# BLCTRL20.net
KiCad netlist of a schematic drawn in EAGLE
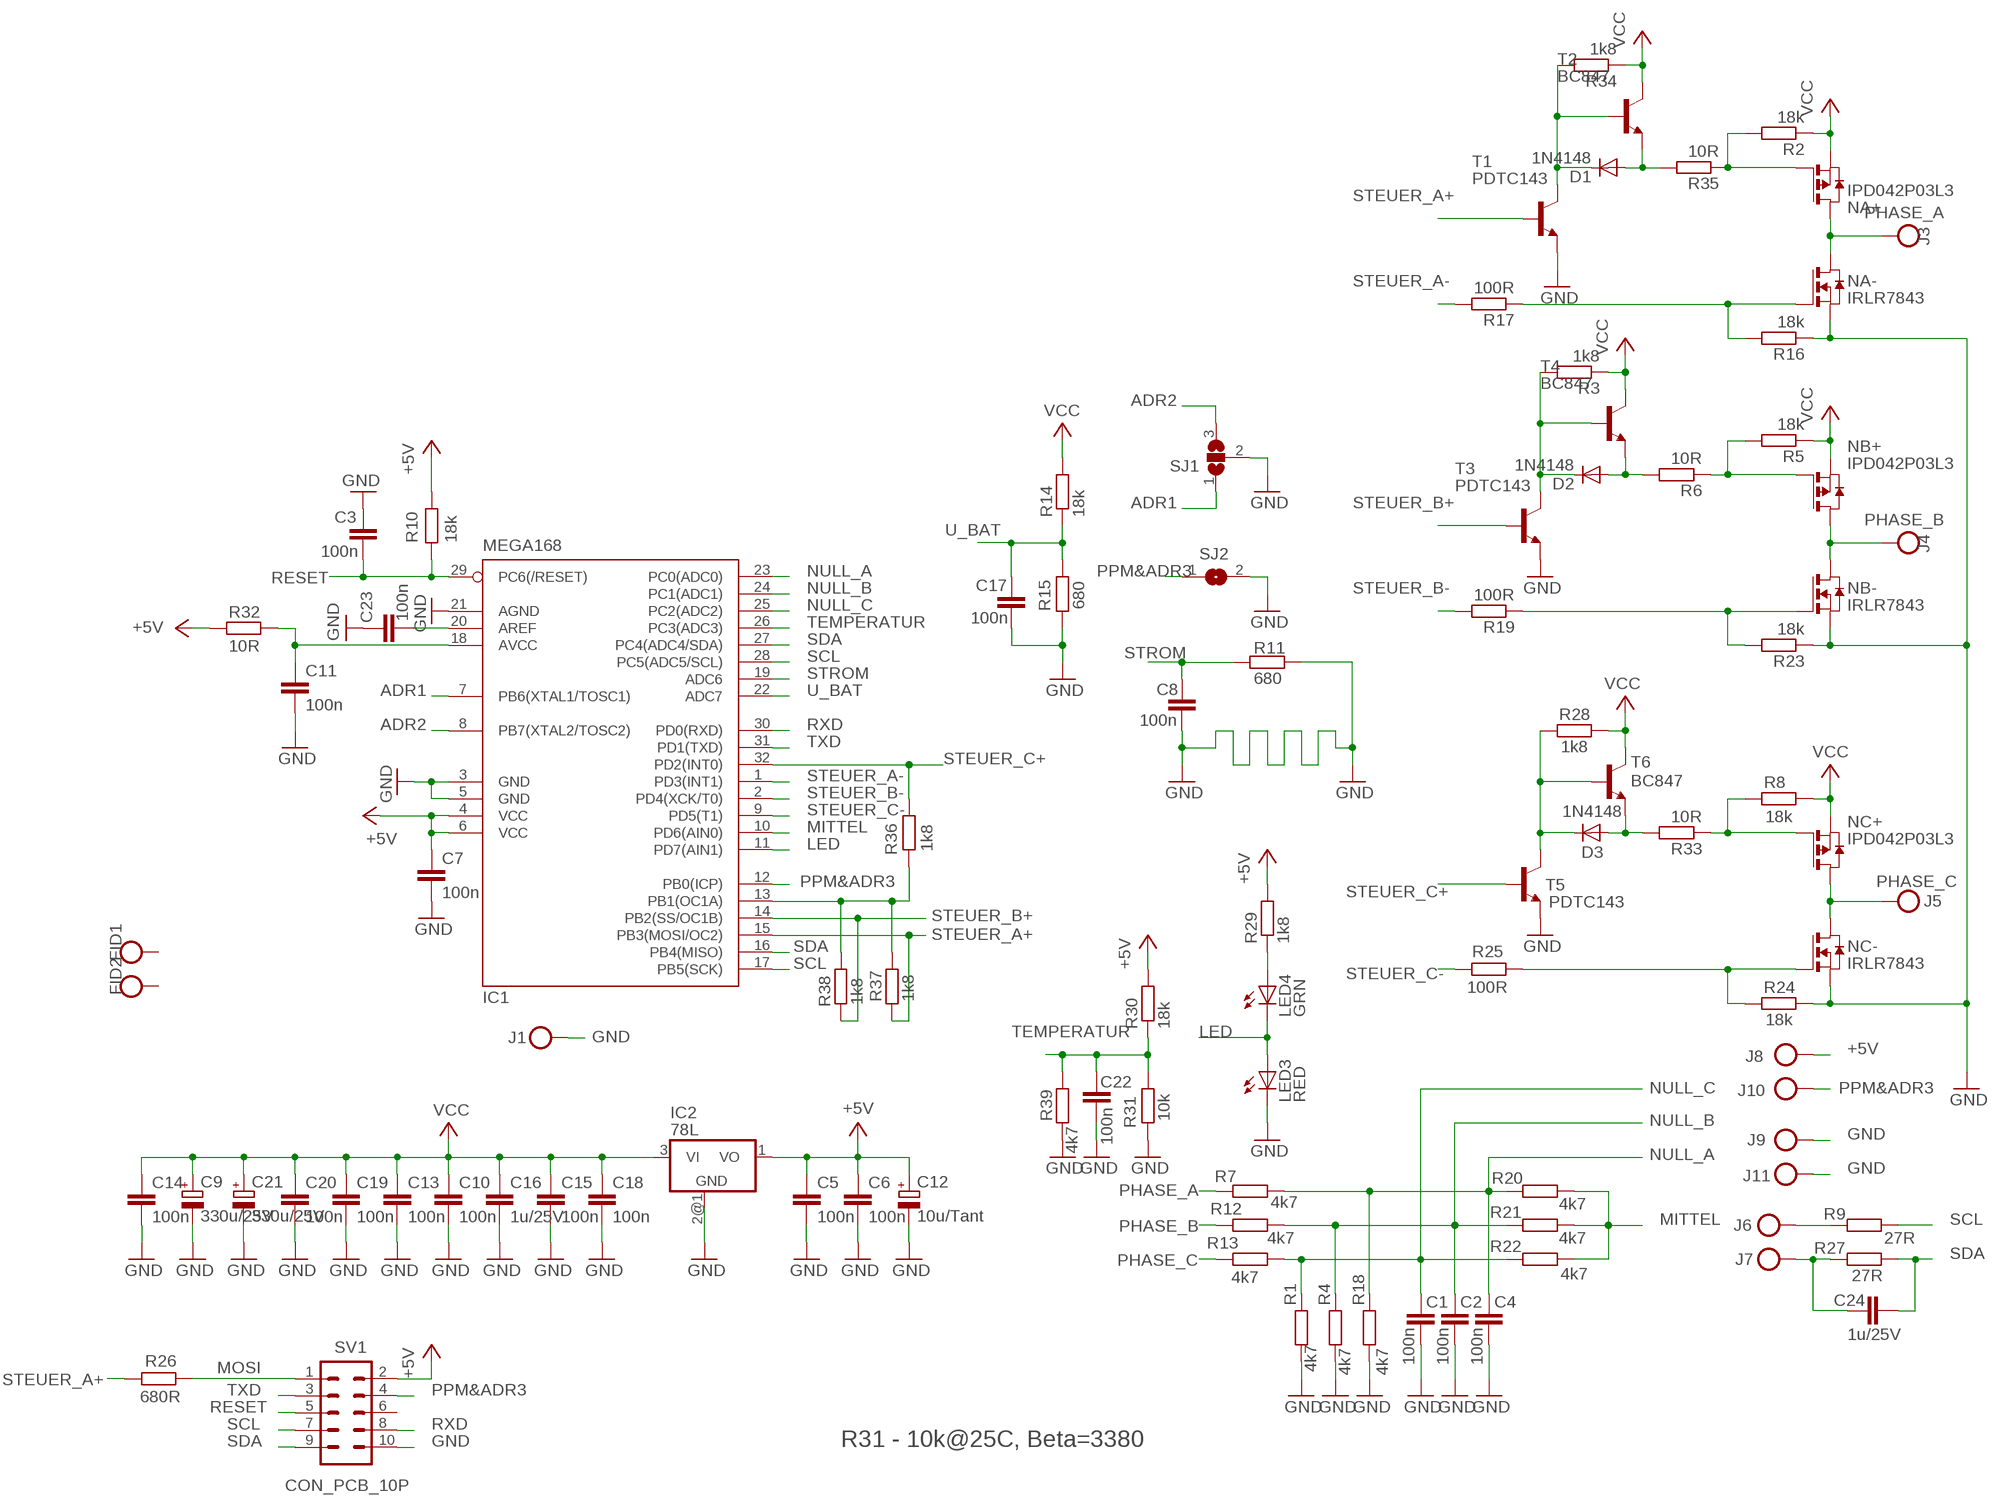
[diagram p0: schematic, sheet 1]

(export (version "E")
  (design (tool "Eeschema 10.0.6"))
  (components
    (comp (ref "C1")
      (value "100n")
      (footprint "eagle-import:C0603")
      (libsource (lib "eagle-import") (part "C-EUC0603"))
    )
    (comp (ref "C2")
      (value "100n")
      (footprint "eagle-import:C0603")
      (libsource (lib "eagle-import") (part "C-EUC0603"))
    )
    (comp (ref "C3")
      (value "100n")
      (footprint "eagle-import:C0603")
      (libsource (lib "eagle-import") (part "C-EUC0603"))
    )
    (comp (ref "C4")
      (value "100n")
      (footprint "eagle-import:C0603")
      (libsource (lib "eagle-import") (part "C-EUC0603"))
    )
    (comp (ref "C5")
      (value "100n")
      (footprint "eagle-import:C0603")
      (libsource (lib "eagle-import") (part "C-EUC0603"))
    )
    (comp (ref "C6")
      (value "100n")
      (footprint "eagle-import:C0603")
      (libsource (lib "eagle-import") (part "C-EUC0603"))
    )
    (comp (ref "C7")
      (value "100n")
      (footprint "eagle-import:C0603")
      (libsource (lib "eagle-import") (part "C-EUC0603"))
    )
    (comp (ref "C8")
      (value "100n")
      (footprint "eagle-import:C0603")
      (libsource (lib "eagle-import") (part "C-EUC0603"))
    )
    (comp (ref "C9")
      (value "330u/25V")
      (footprint "eagle-import:E2,5-5")
      (libsource (lib "eagle-import") (part "CPOL-EUE2.5-5"))
    )
    (comp (ref "C10")
      (value "100n")
      (footprint "eagle-import:C0603")
      (libsource (lib "eagle-import") (part "C-EUC0603"))
    )
    (comp (ref "C11")
      (value "100n")
      (footprint "eagle-import:C0603")
      (libsource (lib "eagle-import") (part "C-EUC0603"))
    )
    (comp (ref "C12")
      (value "10u/Tant")
      (footprint "eagle-import:PANASONIC_B")
      (libsource (lib "eagle-import") (part "CPOL-EUB"))
    )
    (comp (ref "C13")
      (value "100n")
      (footprint "eagle-import:C0603")
      (libsource (lib "eagle-import") (part "C-EUC0603"))
    )
    (comp (ref "C14")
      (value "100n")
      (footprint "eagle-import:C0603")
      (libsource (lib "eagle-import") (part "C-EUC0603"))
    )
    (comp (ref "C15")
      (value "100n")
      (footprint "eagle-import:C0603")
      (libsource (lib "eagle-import") (part "C-EUC0603"))
    )
    (comp (ref "C16")
      (value "1u/25V")
      (footprint "eagle-import:C0603")
      (libsource (lib "eagle-import") (part "C-EUC0603"))
    )
    (comp (ref "C17")
      (value "100n")
      (footprint "eagle-import:C0603")
      (libsource (lib "eagle-import") (part "C-EUC0603"))
    )
    (comp (ref "C18")
      (value "100n")
      (footprint "eagle-import:C0603")
      (libsource (lib "eagle-import") (part "C-EUC0603"))
    )
    (comp (ref "C19")
      (value "100n")
      (footprint "eagle-import:C0603")
      (libsource (lib "eagle-import") (part "C-EUC0603"))
    )
    (comp (ref "C20")
      (value "100n")
      (footprint "eagle-import:C0603")
      (libsource (lib "eagle-import") (part "C-EUC0603"))
    )
    (comp (ref "C21")
      (value "330u/25V")
      (footprint "eagle-import:E2,5-5")
      (libsource (lib "eagle-import") (part "CPOL-EUE2.5-5"))
    )
    (comp (ref "C22")
      (value "100n")
      (footprint "eagle-import:C0603")
      (libsource (lib "eagle-import") (part "C-EUC0603"))
    )
    (comp (ref "C23")
      (value "100n")
      (footprint "eagle-import:C0603")
      (libsource (lib "eagle-import") (part "C-EUC0603"))
    )
    (comp (ref "C24")
      (value "1u/25V")
      (footprint "eagle-import:C0603")
      (libsource (lib "eagle-import") (part "C-EUC0603"))
    )
    (comp (ref "D1")
      (value "1N4148")
      (footprint "eagle-import:SOD323-W")
      (libsource (lib "eagle-import") (part "DIODE-SOD323-W"))
    )
    (comp (ref "D2")
      (value "1N4148")
      (footprint "eagle-import:SOD323-W")
      (libsource (lib "eagle-import") (part "DIODE-SOD323-W"))
    )
    (comp (ref "D3")
      (value "1N4148")
      (footprint "eagle-import:SOD323-W")
      (libsource (lib "eagle-import") (part "DIODE-SOD323-W"))
    )
    (comp (ref "FID1")
      (value "FIDUCIAL")
      (footprint "eagle-import:FIDUCIAL_MARK")
      (libsource (lib "eagle-import") (part "FIDUCIAL"))
    )
    (comp (ref "FID2")
      (value "FIDUCIAL")
      (footprint "eagle-import:FIDUCIAL_MARK")
      (libsource (lib "eagle-import") (part "FIDUCIAL"))
    )
    (comp (ref "IC1")
      (value "MEGA168")
      (footprint "eagle-import:TQFP32-08")
      (libsource (lib "eagle-import") (part "MEGA168"))
    )
    (comp (ref "IC2")
      (value "78L")
      (footprint "eagle-import:SOT89")
      (libsource (lib "eagle-import") (part "78L"))
    )
    (comp (ref "J1")
      (value "SMDPAD40X20")
      (footprint "eagle-import:PAD40X20")
      (libsource (lib "eagle-import") (part "SMDPAD40X20"))
    )
    (comp (ref "J3")
      (value "SMDPAD40X20")
      (footprint "eagle-import:PAD40X20")
      (libsource (lib "eagle-import") (part "SMDPAD40X20"))
    )
    (comp (ref "J4")
      (value "SMDPAD40X20")
      (footprint "eagle-import:PAD40X20")
      (libsource (lib "eagle-import") (part "SMDPAD40X20"))
    )
    (comp (ref "J5")
      (value "SMDPAD40X20")
      (footprint "eagle-import:PAD40X20")
      (libsource (lib "eagle-import") (part "SMDPAD40X20"))
    )
    (comp (ref "J6")
      (value "SE11")
      (footprint "eagle-import:SE11")
      (libsource (lib "eagle-import") (part "SE11"))
    )
    (comp (ref "J7")
      (value "SE11")
      (footprint "eagle-import:SE11")
      (libsource (lib "eagle-import") (part "SE11"))
    )
    (comp (ref "J8")
      (value "SMDPAD25X25")
      (footprint "eagle-import:PAD24X15")
      (libsource (lib "eagle-import") (part "SMDPAD25X25"))
    )
    (comp (ref "J9")
      (value "SMDPAD25X25")
      (footprint "eagle-import:PAD24X15")
      (libsource (lib "eagle-import") (part "SMDPAD25X25"))
    )
    (comp (ref "J10")
      (value "SMDPAD25X25")
      (footprint "eagle-import:PAD24X15")
      (libsource (lib "eagle-import") (part "SMDPAD25X25"))
    )
    (comp (ref "J11")
      (value "SMDPAD24X12")
      (footprint "eagle-import:PAD24X12")
      (libsource (lib "eagle-import") (part "SMDPAD24X12"))
    )
    (comp (ref "LED3")
      (value "RED")
      (footprint "eagle-import:CHIPLED_0603")
      (libsource (lib "eagle-import") (part "LEDCHIPLED_0603"))
    )
    (comp (ref "LED4")
      (value "GRN")
      (footprint "eagle-import:CHIPLED_0603")
      (libsource (lib "eagle-import") (part "LEDCHIPLED_0603"))
    )
    (comp (ref "NA+")
      (value "IPD042P03L3")
      (footprint "eagle-import:TO252")
      (libsource (lib "eagle-import") (part "IPD042P03L3"))
    )
    (comp (ref "NA-")
      (value "IRLR7843")
      (footprint "eagle-import:TO252")
      (libsource (lib "eagle-import") (part "IRLR7843"))
    )
    (comp (ref "NB+")
      (value "IPD042P03L3")
      (footprint "eagle-import:TO252")
      (libsource (lib "eagle-import") (part "IPD042P03L3"))
    )
    (comp (ref "NB-")
      (value "IRLR7843")
      (footprint "eagle-import:TO252")
      (libsource (lib "eagle-import") (part "IRLR7843"))
    )
    (comp (ref "NC+")
      (value "IPD042P03L3")
      (footprint "eagle-import:TO252")
      (libsource (lib "eagle-import") (part "IPD042P03L3"))
    )
    (comp (ref "NC-")
      (value "IRLR7843")
      (footprint "eagle-import:TO252")
      (libsource (lib "eagle-import") (part "IRLR7843"))
    )
    (comp (ref "R1")
      (value "4k7")
      (footprint "eagle-import:R0603")
      (libsource (lib "eagle-import") (part "R-EU_R0603"))
    )
    (comp (ref "R2")
      (value "18k")
      (footprint "eagle-import:R0805")
      (libsource (lib "eagle-import") (part "R-EU_R0805"))
    )
    (comp (ref "R3")
      (value "1k8")
      (footprint "eagle-import:R0603")
      (libsource (lib "eagle-import") (part "R-EU_R0603"))
    )
    (comp (ref "R4")
      (value "4k7")
      (footprint "eagle-import:R0603")
      (libsource (lib "eagle-import") (part "R-EU_R0603"))
    )
    (comp (ref "R5")
      (value "18k")
      (footprint "eagle-import:R0805")
      (libsource (lib "eagle-import") (part "R-EU_R0805"))
    )
    (comp (ref "R6")
      (value "10R")
      (footprint "eagle-import:R0603")
      (libsource (lib "eagle-import") (part "R-EU_R0603"))
    )
    (comp (ref "R7")
      (value "4k7")
      (footprint "eagle-import:R0603")
      (libsource (lib "eagle-import") (part "R-EU_R0603"))
    )
    (comp (ref "R8")
      (value "18k")
      (footprint "eagle-import:R0805")
      (libsource (lib "eagle-import") (part "R-EU_R0805"))
    )
    (comp (ref "R9")
      (value "27R")
      (footprint "eagle-import:R0603")
      (libsource (lib "eagle-import") (part "R-EU_R0603"))
    )
    (comp (ref "R10")
      (value "18k")
      (footprint "eagle-import:R0603")
      (libsource (lib "eagle-import") (part "R-EU_R0603"))
    )
    (comp (ref "R11")
      (value "680")
      (footprint "eagle-import:R0603")
      (libsource (lib "eagle-import") (part "R-EU_R0603"))
    )
    (comp (ref "R12")
      (value "4k7")
      (footprint "eagle-import:R0603")
      (libsource (lib "eagle-import") (part "R-EU_R0603"))
    )
    (comp (ref "R13")
      (value "4k7")
      (footprint "eagle-import:R0603")
      (libsource (lib "eagle-import") (part "R-EU_R0603"))
    )
    (comp (ref "R14")
      (value "18k")
      (footprint "eagle-import:R0603")
      (libsource (lib "eagle-import") (part "R-EU_R0603"))
    )
    (comp (ref "R15")
      (value "680")
      (footprint "eagle-import:R0603")
      (libsource (lib "eagle-import") (part "R-EU_R0603"))
    )
    (comp (ref "R16")
      (value "18k")
      (footprint "eagle-import:R0805")
      (libsource (lib "eagle-import") (part "R-EU_R0805"))
    )
    (comp (ref "R17")
      (value "100R")
      (footprint "eagle-import:R0603")
      (libsource (lib "eagle-import") (part "R-EU_R0603"))
    )
    (comp (ref "R18")
      (value "4k7")
      (footprint "eagle-import:R0603")
      (libsource (lib "eagle-import") (part "R-EU_R0603"))
    )
    (comp (ref "R19")
      (value "100R")
      (footprint "eagle-import:R0603")
      (libsource (lib "eagle-import") (part "R-EU_R0603"))
    )
    (comp (ref "R20")
      (value "4k7")
      (footprint "eagle-import:R0603")
      (libsource (lib "eagle-import") (part "R-EU_R0603"))
    )
    (comp (ref "R21")
      (value "4k7")
      (footprint "eagle-import:R0603")
      (libsource (lib "eagle-import") (part "R-EU_R0603"))
    )
    (comp (ref "R22")
      (value "4k7")
      (footprint "eagle-import:R0603")
      (libsource (lib "eagle-import") (part "R-EU_R0603"))
    )
    (comp (ref "R23")
      (value "18k")
      (footprint "eagle-import:R0805")
      (libsource (lib "eagle-import") (part "R-EU_R0805"))
    )
    (comp (ref "R24")
      (value "18k")
      (footprint "eagle-import:R0805")
      (libsource (lib "eagle-import") (part "R-EU_R0805"))
    )
    (comp (ref "R25")
      (value "100R")
      (footprint "eagle-import:R0603")
      (libsource (lib "eagle-import") (part "R-EU_R0603"))
    )
    (comp (ref "R26")
      (value "680R")
      (footprint "eagle-import:R0603")
      (libsource (lib "eagle-import") (part "R-EU_R0603"))
    )
    (comp (ref "R27")
      (value "27R")
      (footprint "eagle-import:R0603")
      (libsource (lib "eagle-import") (part "R-EU_R0603"))
    )
    (comp (ref "R28")
      (value "1k8")
      (footprint "eagle-import:R0603")
      (libsource (lib "eagle-import") (part "R-EU_R0603"))
    )
    (comp (ref "R29")
      (value "1k8")
      (footprint "eagle-import:R0603")
      (libsource (lib "eagle-import") (part "R-EU_R0603"))
    )
    (comp (ref "R30")
      (value "18k")
      (footprint "eagle-import:R0603")
      (libsource (lib "eagle-import") (part "R-EU_R0603"))
    )
    (comp (ref "R31")
      (value "10k")
      (footprint "eagle-import:R0603")
      (libsource (lib "eagle-import") (part "R-EU_R0603"))
    )
    (comp (ref "R32")
      (value "10R")
      (footprint "eagle-import:R0603")
      (libsource (lib "eagle-import") (part "R-EU_R0603"))
    )
    (comp (ref "R33")
      (value "10R")
      (footprint "eagle-import:R0603")
      (libsource (lib "eagle-import") (part "R-EU_R0603"))
    )
    (comp (ref "R34")
      (value "1k8")
      (footprint "eagle-import:R0603")
      (libsource (lib "eagle-import") (part "R-EU_R0603"))
    )
    (comp (ref "R35")
      (value "10R")
      (footprint "eagle-import:R0603")
      (libsource (lib "eagle-import") (part "R-EU_R0603"))
    )
    (comp (ref "R36")
      (value "1k8")
      (footprint "eagle-import:R0603")
      (libsource (lib "eagle-import") (part "R-EU_R0603"))
    )
    (comp (ref "R37")
      (value "1k8")
      (footprint "eagle-import:R0603")
      (libsource (lib "eagle-import") (part "R-EU_R0603"))
    )
    (comp (ref "R38")
      (value "1k8")
      (footprint "eagle-import:R0603")
      (libsource (lib "eagle-import") (part "R-EU_R0603"))
    )
    (comp (ref "R39")
      (value "4k7")
      (footprint "eagle-import:R0603")
      (libsource (lib "eagle-import") (part "R-EU_R0603"))
    )
    (comp (ref "SJ1")
      (value "SJ2W")
      (footprint "eagle-import:SJ_2")
      (libsource (lib "eagle-import") (part "SJ2W"))
    )
    (comp (ref "SJ2") (value "SJ") (footprint "eagle-import:SJ") (libsource (lib "eagle-import") (part "SJ")))
    (comp (ref "SV1")
      (value "CON_PCB_10P")
      (footprint "eagle-import:BOARD_CON_SMD")
      (libsource (lib "eagle-import") (part "CON_PCB_10P"))
    )
    (comp (ref "T1")
      (value "PDTC143")
      (footprint "eagle-import:SC75_INFINEON")
      (libsource (lib "eagle-import") (part "PDTC143"))
    )
    (comp (ref "T2")
      (value "BC847")
      (footprint "eagle-import:SC75_INFINEON")
      (libsource (lib "eagle-import") (part "BC847"))
    )
    (comp (ref "T3")
      (value "PDTC143")
      (footprint "eagle-import:SC75_INFINEON")
      (libsource (lib "eagle-import") (part "PDTC143"))
    )
    (comp (ref "T4")
      (value "BC847")
      (footprint "eagle-import:SC75_INFINEON")
      (libsource (lib "eagle-import") (part "BC847"))
    )
    (comp (ref "T5")
      (value "PDTC143")
      (footprint "eagle-import:SC75_INFINEON")
      (libsource (lib "eagle-import") (part "PDTC143"))
    )
    (comp (ref "T6")
      (value "BC847")
      (footprint "eagle-import:SC75_INFINEON")
      (libsource (lib "eagle-import") (part "BC847"))
    )
  )
  (nets
    (net (code "1") (name "+5V") (class "Default")
      (node (ref "C12") (pin "+") (pinfunction "+_+") (pintype "passive"))
      (node (ref "C5") (pin "1") (pinfunction "1_1") (pintype "passive"))
      (node (ref "C6") (pin "1") (pinfunction "1_1") (pintype "passive"))
      (node (ref "C7") (pin "1") (pinfunction "1_1") (pintype "passive"))
      (node (ref "IC1") (pin "4") (pinfunction "VCC_4") (pintype "power_in"))
      (node (ref "IC1") (pin "6") (pinfunction "VCC_6") (pintype "power_in"))
      (node (ref "IC2") (pin "1") (pinfunction "VO_1") (pintype "passive"))
      (node (ref "J8") (pin "P$1") (pinfunction "MP_P$1") (pintype "passive"))
      (node (ref "R10") (pin "2") (pinfunction "2_2") (pintype "passive"))
      (node (ref "R29") (pin "2") (pinfunction "2_2") (pintype "passive"))
      (node (ref "R30") (pin "2") (pinfunction "2_2") (pintype "passive"))
      (node (ref "R32") (pin "2") (pinfunction "2_2") (pintype "passive"))
      (node (ref "SV1") (pin "2") (pinfunction "2_2") (pintype "passive"))
    )
    (net (code "2") (name "/ADR1") (class "Default")
      (node (ref "IC1") (pin "7") (pinfunction "PB6(XTAL1/TOSC1)_7") (pintype "bidirectional"))
      (node (ref "SJ1") (pin "1") (pinfunction "1_1") (pintype "passive"))
    )
    (net (code "3") (name "/ADR2") (class "Default")
      (node (ref "IC1") (pin "8") (pinfunction "PB7(XTAL2/TOSC2)_8") (pintype "bidirectional"))
      (node (ref "SJ1") (pin "3") (pinfunction "3_3") (pintype "passive"))
    )
    (net (code "4") (name "/LED") (class "Default")
      (node (ref "IC1") (pin "11") (pinfunction "PD7(AIN1)_11") (pintype "bidirectional"))
      (node (ref "LED3") (pin "A") (pinfunction "A_A") (pintype "passive"))
      (node (ref "LED4") (pin "C") (pinfunction "C_C") (pintype "passive"))
    )
    (net (code "5") (name "/MITTEL") (class "Default")
      (node (ref "IC1") (pin "10") (pinfunction "PD6(AIN0)_10") (pintype "bidirectional"))
      (node (ref "R20") (pin "1") (pinfunction "1_1") (pintype "passive"))
      (node (ref "R21") (pin "1") (pinfunction "1_1") (pintype "passive"))
      (node (ref "R22") (pin "1") (pinfunction "1_1") (pintype "passive"))
    )
    (net (code "6") (name "/MOSI") (class "Default")
      (node (ref "R26") (pin "1") (pinfunction "1_1") (pintype "passive"))
      (node (ref "SV1") (pin "1") (pinfunction "1_1") (pintype "passive"))
    )
    (net (code "7") (name "/NULL_A") (class "Default")
      (node (ref "C4") (pin "1") (pinfunction "1_1") (pintype "passive"))
      (node (ref "IC1") (pin "23") (pinfunction "PC0(ADC0)_23") (pintype "bidirectional"))
      (node (ref "R18") (pin "2") (pinfunction "2_2") (pintype "passive"))
      (node (ref "R20") (pin "2") (pinfunction "2_2") (pintype "passive"))
      (node (ref "R7") (pin "1") (pinfunction "1_1") (pintype "passive"))
    )
    (net (code "8") (name "/NULL_B") (class "Default")
      (node (ref "C2") (pin "1") (pinfunction "1_1") (pintype "passive"))
      (node (ref "IC1") (pin "24") (pinfunction "PC1(ADC1)_24") (pintype "bidirectional"))
      (node (ref "R12") (pin "1") (pinfunction "1_1") (pintype "passive"))
      (node (ref "R21") (pin "2") (pinfunction "2_2") (pintype "passive"))
      (node (ref "R4") (pin "2") (pinfunction "2_2") (pintype "passive"))
    )
    (net (code "9") (name "/NULL_C") (class "Default")
      (node (ref "C1") (pin "1") (pinfunction "1_1") (pintype "passive"))
      (node (ref "IC1") (pin "25") (pinfunction "PC2(ADC2)_25") (pintype "bidirectional"))
      (node (ref "R1") (pin "2") (pinfunction "2_2") (pintype "passive"))
      (node (ref "R13") (pin "1") (pinfunction "1_1") (pintype "passive"))
      (node (ref "R22") (pin "2") (pinfunction "2_2") (pintype "passive"))
    )
    (net (code "10") (name "/PHASE_A") (class "Default")
      (node (ref "J3") (pin "P$1") (pinfunction "MP_P$1") (pintype "passive"))
      (node (ref "NA+") (pin "2") (pinfunction "D_2") (pintype "passive"))
      (node (ref "NA-") (pin "2") (pinfunction "D_2") (pintype "passive"))
      (node (ref "R7") (pin "2") (pinfunction "2_2") (pintype "passive"))
    )
    (net (code "11") (name "/PHASE_B") (class "Default")
      (node (ref "J4") (pin "P$1") (pinfunction "MP_P$1") (pintype "passive"))
      (node (ref "NB+") (pin "2") (pinfunction "D_2") (pintype "passive"))
      (node (ref "NB-") (pin "2") (pinfunction "D_2") (pintype "passive"))
      (node (ref "R12") (pin "2") (pinfunction "2_2") (pintype "passive"))
    )
    (net (code "12") (name "/PHASE_C") (class "Default")
      (node (ref "J5") (pin "P$1") (pinfunction "MP_P$1") (pintype "passive"))
      (node (ref "NC+") (pin "2") (pinfunction "D_2") (pintype "passive"))
      (node (ref "NC-") (pin "2") (pinfunction "D_2") (pintype "passive"))
      (node (ref "R13") (pin "2") (pinfunction "2_2") (pintype "passive"))
    )
    (net (code "13") (name "/PPM&ADR3") (class "Default")
      (node (ref "IC1") (pin "12") (pinfunction "PB0(ICP)_12") (pintype "bidirectional"))
      (node (ref "J10") (pin "P$1") (pinfunction "MP_P$1") (pintype "passive"))
      (node (ref "SJ2") (pin "1") (pinfunction "1_1") (pintype "passive"))
      (node (ref "SV1") (pin "4") (pinfunction "4_4") (pintype "passive"))
    )
    (net (code "14") (name "/RESET") (class "Default")
      (node (ref "C3") (pin "2") (pinfunction "2_2") (pintype "passive"))
      (node (ref "IC1") (pin "29") (pinfunction "PC6(/RESET)_29") (pintype "bidirectional"))
      (node (ref "R10") (pin "1") (pinfunction "1_1") (pintype "passive"))
      (node (ref "SV1") (pin "5") (pinfunction "5_5") (pintype "passive"))
    )
    (net (code "15") (name "/RXD") (class "Default")
      (node (ref "IC1") (pin "30") (pinfunction "PD0(RXD)_30") (pintype "bidirectional"))
      (node (ref "SV1") (pin "8") (pinfunction "8_8") (pintype "passive"))
    )
    (net (code "16") (name "/SCL") (class "Default")
      (node (ref "IC1") (pin "17") (pinfunction "PB5(SCK)_17") (pintype "bidirectional"))
      (node (ref "IC1") (pin "28") (pinfunction "PC5(ADC5/SCL)_28") (pintype "bidirectional"))
      (node (ref "R9") (pin "1") (pinfunction "1_1") (pintype "passive"))
      (node (ref "SV1") (pin "7") (pinfunction "7_7") (pintype "passive"))
    )
    (net (code "17") (name "/SDA") (class "Default")
      (node (ref "C24") (pin "1") (pinfunction "1_1") (pintype "passive"))
      (node (ref "IC1") (pin "16") (pinfunction "PB4(MISO)_16") (pintype "bidirectional"))
      (node (ref "IC1") (pin "27") (pinfunction "PC4(ADC4/SDA)_27") (pintype "bidirectional"))
      (node (ref "R27") (pin "1") (pinfunction "1_1") (pintype "passive"))
      (node (ref "SV1") (pin "9") (pinfunction "9_9") (pintype "passive"))
    )
    (net (code "18") (name "/STEUER_A+") (class "Default")
      (node (ref "IC1") (pin "15") (pinfunction "PB3(MOSI/OC2)_15") (pintype "bidirectional"))
      (node (ref "R26") (pin "2") (pinfunction "2_2") (pintype "passive"))
      (node (ref "R37") (pin "1") (pinfunction "1_1") (pintype "passive"))
      (node (ref "T1") (pin "1") (pinfunction "B_1") (pintype "passive"))
    )
    (net (code "19") (name "/STEUER_A-") (class "Default")
      (node (ref "IC1") (pin "1") (pinfunction "PD3(INT1)_1") (pintype "bidirectional"))
      (node (ref "R17") (pin "2") (pinfunction "2_2") (pintype "passive"))
    )
    (net (code "20") (name "/STEUER_B+") (class "Default")
      (node (ref "IC1") (pin "14") (pinfunction "PB2(SS/OC1B)_14") (pintype "bidirectional"))
      (node (ref "R38") (pin "1") (pinfunction "1_1") (pintype "passive"))
      (node (ref "T3") (pin "1") (pinfunction "B_1") (pintype "passive"))
    )
    (net (code "21") (name "/STEUER_B-") (class "Default")
      (node (ref "IC1") (pin "2") (pinfunction "PD4(XCK/T0)_2") (pintype "bidirectional"))
      (node (ref "R19") (pin "2") (pinfunction "2_2") (pintype "passive"))
    )
    (net (code "22") (name "/STEUER_C+") (class "Default")
      (node (ref "IC1") (pin "32") (pinfunction "PD2(INT0)_32") (pintype "bidirectional"))
      (node (ref "R36") (pin "2") (pinfunction "2_2") (pintype "passive"))
      (node (ref "T5") (pin "1") (pinfunction "B_1") (pintype "passive"))
    )
    (net (code "23") (name "/STEUER_C-") (class "Default")
      (node (ref "IC1") (pin "9") (pinfunction "PD5(T1)_9") (pintype "bidirectional"))
      (node (ref "R25") (pin "2") (pinfunction "2_2") (pintype "passive"))
    )
    (net (code "24") (name "/STROM") (class "Default")
      (node (ref "C8") (pin "1") (pinfunction "1_1") (pintype "passive"))
      (node (ref "IC1") (pin "19") (pinfunction "ADC6_19") (pintype "bidirectional"))
      (node (ref "R11") (pin "2") (pinfunction "2_2") (pintype "passive"))
    )
    (net (code "25") (name "/TEMPERATUR") (class "Default")
      (node (ref "C22") (pin "1") (pinfunction "1_1") (pintype "passive"))
      (node (ref "IC1") (pin "26") (pinfunction "PC3(ADC3)_26") (pintype "bidirectional"))
      (node (ref "R30") (pin "1") (pinfunction "1_1") (pintype "passive"))
      (node (ref "R31") (pin "2") (pinfunction "2_2") (pintype "passive"))
      (node (ref "R39") (pin "2") (pinfunction "2_2") (pintype "passive"))
    )
    (net (code "26") (name "/TXD") (class "Default")
      (node (ref "IC1") (pin "31") (pinfunction "PD1(TXD)_31") (pintype "bidirectional"))
      (node (ref "SV1") (pin "3") (pinfunction "3_3") (pintype "passive"))
    )
    (net (code "27") (name "/U_BAT") (class "Default")
      (node (ref "C17") (pin "1") (pinfunction "1_1") (pintype "passive"))
      (node (ref "IC1") (pin "22") (pinfunction "ADC7_22") (pintype "bidirectional"))
      (node (ref "R14") (pin "1") (pinfunction "1_1") (pintype "passive"))
      (node (ref "R15") (pin "2") (pinfunction "2_2") (pintype "passive"))
    )
    (net (code "28") (name "GND") (class "Default")
      (node (ref "C1") (pin "2") (pinfunction "2_2") (pintype "passive"))
      (node (ref "C10") (pin "2") (pinfunction "2_2") (pintype "passive"))
      (node (ref "C11") (pin "2") (pinfunction "2_2") (pintype "passive"))
      (node (ref "C12") (pin "-") (pinfunction "-_-") (pintype "passive"))
      (node (ref "C13") (pin "2") (pinfunction "2_2") (pintype "passive"))
      (node (ref "C14") (pin "2") (pinfunction "2_2") (pintype "passive"))
      (node (ref "C15") (pin "2") (pinfunction "2_2") (pintype "passive"))
      (node (ref "C16") (pin "2") (pinfunction "2_2") (pintype "passive"))
      (node (ref "C17") (pin "2") (pinfunction "2_2") (pintype "passive"))
      (node (ref "C18") (pin "2") (pinfunction "2_2") (pintype "passive"))
      (node (ref "C19") (pin "2") (pinfunction "2_2") (pintype "passive"))
      (node (ref "C2") (pin "2") (pinfunction "2_2") (pintype "passive"))
      (node (ref "C20") (pin "2") (pinfunction "2_2") (pintype "passive"))
      (node (ref "C21") (pin "-") (pinfunction "-_-") (pintype "passive"))
      (node (ref "C22") (pin "2") (pinfunction "2_2") (pintype "passive"))
      (node (ref "C23") (pin "1") (pinfunction "1_1") (pintype "passive"))
      (node (ref "C3") (pin "1") (pinfunction "1_1") (pintype "passive"))
      (node (ref "C4") (pin "2") (pinfunction "2_2") (pintype "passive"))
      (node (ref "C5") (pin "2") (pinfunction "2_2") (pintype "passive"))
      (node (ref "C6") (pin "2") (pinfunction "2_2") (pintype "passive"))
      (node (ref "C7") (pin "2") (pinfunction "2_2") (pintype "passive"))
      (node (ref "C8") (pin "2") (pinfunction "2_2") (pintype "passive"))
      (node (ref "C9") (pin "-") (pinfunction "-_-") (pintype "passive"))
      (node (ref "IC1") (pin "21") (pinfunction "AGND_21") (pintype "power_in"))
      (node (ref "IC1") (pin "3") (pinfunction "GND_3") (pintype "power_in"))
      (node (ref "IC1") (pin "5") (pinfunction "GND_5") (pintype "power_in"))
      (node (ref "IC2") (pin "2@1") (pinfunction "GND_2@1") (pintype "passive"))
      (node (ref "J1") (pin "P$1") (pinfunction "MP_P$1") (pintype "passive"))
      (node (ref "J11") (pin "P$1") (pinfunction "MP_P$1") (pintype "passive"))
      (node (ref "J9") (pin "P$1") (pinfunction "MP_P$1") (pintype "passive"))
      (node (ref "LED3") (pin "C") (pinfunction "C_C") (pintype "passive"))
      (node (ref "NA-") (pin "3") (pinfunction "S_3") (pintype "passive"))
      (node (ref "NB-") (pin "3") (pinfunction "S_3") (pintype "passive"))
      (node (ref "NC-") (pin "3") (pinfunction "S_3") (pintype "passive"))
      (node (ref "R1") (pin "1") (pinfunction "1_1") (pintype "passive"))
      (node (ref "R11") (pin "1") (pinfunction "1_1") (pintype "passive"))
      (node (ref "R15") (pin "1") (pinfunction "1_1") (pintype "passive"))
      (node (ref "R16") (pin "1") (pinfunction "1_1") (pintype "passive"))
      (node (ref "R18") (pin "1") (pinfunction "1_1") (pintype "passive"))
      (node (ref "R23") (pin "1") (pinfunction "1_1") (pintype "passive"))
      (node (ref "R24") (pin "1") (pinfunction "1_1") (pintype "passive"))
      (node (ref "R31") (pin "1") (pinfunction "1_1") (pintype "passive"))
      (node (ref "R39") (pin "1") (pinfunction "1_1") (pintype "passive"))
      (node (ref "R4") (pin "1") (pinfunction "1_1") (pintype "passive"))
      (node (ref "SJ1") (pin "2") (pinfunction "2_2") (pintype "passive"))
      (node (ref "SJ2") (pin "2") (pinfunction "2_2") (pintype "passive"))
      (node (ref "SV1") (pin "10") (pinfunction "10_10") (pintype "passive"))
      (node (ref "T1") (pin "2") (pinfunction "E_2") (pintype "passive"))
      (node (ref "T3") (pin "2") (pinfunction "E_2") (pintype "passive"))
      (node (ref "T5") (pin "2") (pinfunction "E_2") (pintype "passive"))
    )
    (net (code "29") (name "Net-(C24-Pad2)") (class "Default")
      (node (ref "C24") (pin "2") (pinfunction "2_2") (pintype "passive"))
      (node (ref "J7") (pin "MP") (pinfunction "MP_MP") (pintype "passive"))
      (node (ref "R27") (pin "2") (pinfunction "2_2") (pintype "passive"))
    )
    (net (code "30") (name "Net-(IC1-AREF)") (class "Default")
      (node (ref "C23") (pin "2") (pinfunction "2_2") (pintype "passive"))
      (node (ref "IC1") (pin "20") (pinfunction "AREF_20") (pintype "passive"))
    )
    (net (code "31") (name "Net-(IC1-AVCC)") (class "Default")
      (node (ref "C11") (pin "1") (pinfunction "1_1") (pintype "passive"))
      (node (ref "IC1") (pin "18") (pinfunction "AVCC_18") (pintype "power_in"))
      (node (ref "R32") (pin "1") (pinfunction "1_1") (pintype "passive"))
    )
    (net (code "32") (name "Net-(IC1-PB1(OC1A))") (class "Default")
      (node (ref "IC1") (pin "13") (pinfunction "PB1(OC1A)_13") (pintype "bidirectional"))
      (node (ref "R36") (pin "1") (pinfunction "1_1") (pintype "passive"))
      (node (ref "R37") (pin "2") (pinfunction "2_2") (pintype "passive"))
      (node (ref "R38") (pin "2") (pinfunction "2_2") (pintype "passive"))
    )
    (net (code "33") (name "Net-(J6-PadMP)") (class "Default")
      (node (ref "J6") (pin "MP") (pinfunction "MP_MP") (pintype "passive"))
      (node (ref "R9") (pin "2") (pinfunction "2_2") (pintype "passive"))
    )
    (net (code "34") (name "Net-(LED4-PadA)") (class "Default")
      (node (ref "LED4") (pin "A") (pinfunction "A_A") (pintype "passive"))
      (node (ref "R29") (pin "1") (pinfunction "1_1") (pintype "passive"))
    )
    (net (code "35") (name "Net-(NA+-G)") (class "Default")
      (node (ref "NA+") (pin "1") (pinfunction "G_1") (pintype "passive"))
      (node (ref "R2") (pin "2") (pinfunction "2_2") (pintype "passive"))
      (node (ref "R35") (pin "1") (pinfunction "1_1") (pintype "passive"))
    )
    (net (code "36") (name "Net-(NA--G)") (class "Default")
      (node (ref "NA-") (pin "1") (pinfunction "G_1") (pintype "passive"))
      (node (ref "R16") (pin "2") (pinfunction "2_2") (pintype "passive"))
      (node (ref "R17") (pin "1") (pinfunction "1_1") (pintype "passive"))
    )
    (net (code "37") (name "Net-(NB+-G)") (class "Default")
      (node (ref "NB+") (pin "1") (pinfunction "G_1") (pintype "passive"))
      (node (ref "R5") (pin "2") (pinfunction "2_2") (pintype "passive"))
      (node (ref "R6") (pin "1") (pinfunction "1_1") (pintype "passive"))
    )
    (net (code "38") (name "Net-(NB--G)") (class "Default")
      (node (ref "NB-") (pin "1") (pinfunction "G_1") (pintype "passive"))
      (node (ref "R19") (pin "1") (pinfunction "1_1") (pintype "passive"))
      (node (ref "R23") (pin "2") (pinfunction "2_2") (pintype "passive"))
    )
    (net (code "39") (name "Net-(NC+-G)") (class "Default")
      (node (ref "NC+") (pin "1") (pinfunction "G_1") (pintype "passive"))
      (node (ref "R33") (pin "1") (pinfunction "1_1") (pintype "passive"))
      (node (ref "R8") (pin "2") (pinfunction "2_2") (pintype "passive"))
    )
    (net (code "40") (name "Net-(NC--G)") (class "Default")
      (node (ref "NC-") (pin "1") (pinfunction "G_1") (pintype "passive"))
      (node (ref "R24") (pin "2") (pinfunction "2_2") (pintype "passive"))
      (node (ref "R25") (pin "1") (pinfunction "1_1") (pintype "passive"))
    )
    (net (code "41") (name "Net-(T1-C)") (class "Default")
      (node (ref "D1") (pin "C") (pinfunction "C_C") (pintype "passive"))
      (node (ref "R34") (pin "2") (pinfunction "2_2") (pintype "passive"))
      (node (ref "T1") (pin "3") (pinfunction "C_3") (pintype "passive"))
      (node (ref "T2") (pin "1") (pinfunction "B_1") (pintype "passive"))
    )
    (net (code "42") (name "Net-(T2-E)") (class "Default")
      (node (ref "D1") (pin "A") (pinfunction "A_A") (pintype "passive"))
      (node (ref "R35") (pin "2") (pinfunction "2_2") (pintype "passive"))
      (node (ref "T2") (pin "2") (pinfunction "E_2") (pintype "passive"))
    )
    (net (code "43") (name "Net-(T3-C)") (class "Default")
      (node (ref "D2") (pin "C") (pinfunction "C_C") (pintype "passive"))
      (node (ref "R3") (pin "2") (pinfunction "2_2") (pintype "passive"))
      (node (ref "T3") (pin "3") (pinfunction "C_3") (pintype "passive"))
      (node (ref "T4") (pin "1") (pinfunction "B_1") (pintype "passive"))
    )
    (net (code "44") (name "Net-(T4-E)") (class "Default")
      (node (ref "D2") (pin "A") (pinfunction "A_A") (pintype "passive"))
      (node (ref "R6") (pin "2") (pinfunction "2_2") (pintype "passive"))
      (node (ref "T4") (pin "2") (pinfunction "E_2") (pintype "passive"))
    )
    (net (code "45") (name "Net-(T5-C)") (class "Default")
      (node (ref "D3") (pin "C") (pinfunction "C_C") (pintype "passive"))
      (node (ref "R28") (pin "2") (pinfunction "2_2") (pintype "passive"))
      (node (ref "T5") (pin "3") (pinfunction "C_3") (pintype "passive"))
      (node (ref "T6") (pin "1") (pinfunction "B_1") (pintype "passive"))
    )
    (net (code "46") (name "Net-(T6-E)") (class "Default")
      (node (ref "D3") (pin "A") (pinfunction "A_A") (pintype "passive"))
      (node (ref "R33") (pin "2") (pinfunction "2_2") (pintype "passive"))
      (node (ref "T6") (pin "2") (pinfunction "E_2") (pintype "passive"))
    )
    (net (code "47") (name "VCC") (class "Default")
      (node (ref "C10") (pin "1") (pinfunction "1_1") (pintype "passive"))
      (node (ref "C13") (pin "1") (pinfunction "1_1") (pintype "passive"))
      (node (ref "C14") (pin "1") (pinfunction "1_1") (pintype "passive"))
      (node (ref "C15") (pin "1") (pinfunction "1_1") (pintype "passive"))
      (node (ref "C16") (pin "1") (pinfunction "1_1") (pintype "passive"))
      (node (ref "C18") (pin "1") (pinfunction "1_1") (pintype "passive"))
      (node (ref "C19") (pin "1") (pinfunction "1_1") (pintype "passive"))
      (node (ref "C20") (pin "1") (pinfunction "1_1") (pintype "passive"))
      (node (ref "C21") (pin "+") (pinfunction "+_+") (pintype "passive"))
      (node (ref "C9") (pin "+") (pinfunction "+_+") (pintype "passive"))
      (node (ref "IC2") (pin "3") (pinfunction "VI_3") (pintype "input"))
      (node (ref "NA+") (pin "3") (pinfunction "S_3") (pintype "passive"))
      (node (ref "NB+") (pin "3") (pinfunction "S_3") (pintype "passive"))
      (node (ref "NC+") (pin "3") (pinfunction "S_3") (pintype "passive"))
      (node (ref "R14") (pin "2") (pinfunction "2_2") (pintype "passive"))
      (node (ref "R2") (pin "1") (pinfunction "1_1") (pintype "passive"))
      (node (ref "R28") (pin "1") (pinfunction "1_1") (pintype "passive"))
      (node (ref "R3") (pin "1") (pinfunction "1_1") (pintype "passive"))
      (node (ref "R34") (pin "1") (pinfunction "1_1") (pintype "passive"))
      (node (ref "R5") (pin "1") (pinfunction "1_1") (pintype "passive"))
      (node (ref "R8") (pin "1") (pinfunction "1_1") (pintype "passive"))
      (node (ref "T2") (pin "3") (pinfunction "C_3") (pintype "passive"))
      (node (ref "T4") (pin "3") (pinfunction "C_3") (pintype "passive"))
      (node (ref "T6") (pin "3") (pinfunction "C_3") (pintype "passive"))
    )
    (net (code "48") (name "unconnected-(FID1-MP-PadP$1)") (class "Default")
      (node (ref "FID1") (pin "P$1") (pinfunction "MP_P$1") (pintype "passive"))
    )
    (net (code "49") (name "unconnected-(FID2-MP-PadP$1)") (class "Default")
      (node (ref "FID2") (pin "P$1") (pinfunction "MP_P$1") (pintype "passive"))
    )
    (net (code "50") (name "unconnected-(SV1-Pad6)") (class "Default")
      (node (ref "SV1") (pin "6") (pinfunction "6_6") (pintype "passive"))
    )
  )
)
